# schematic.net
KiCad netlist of a schematic drawn in EAGLE
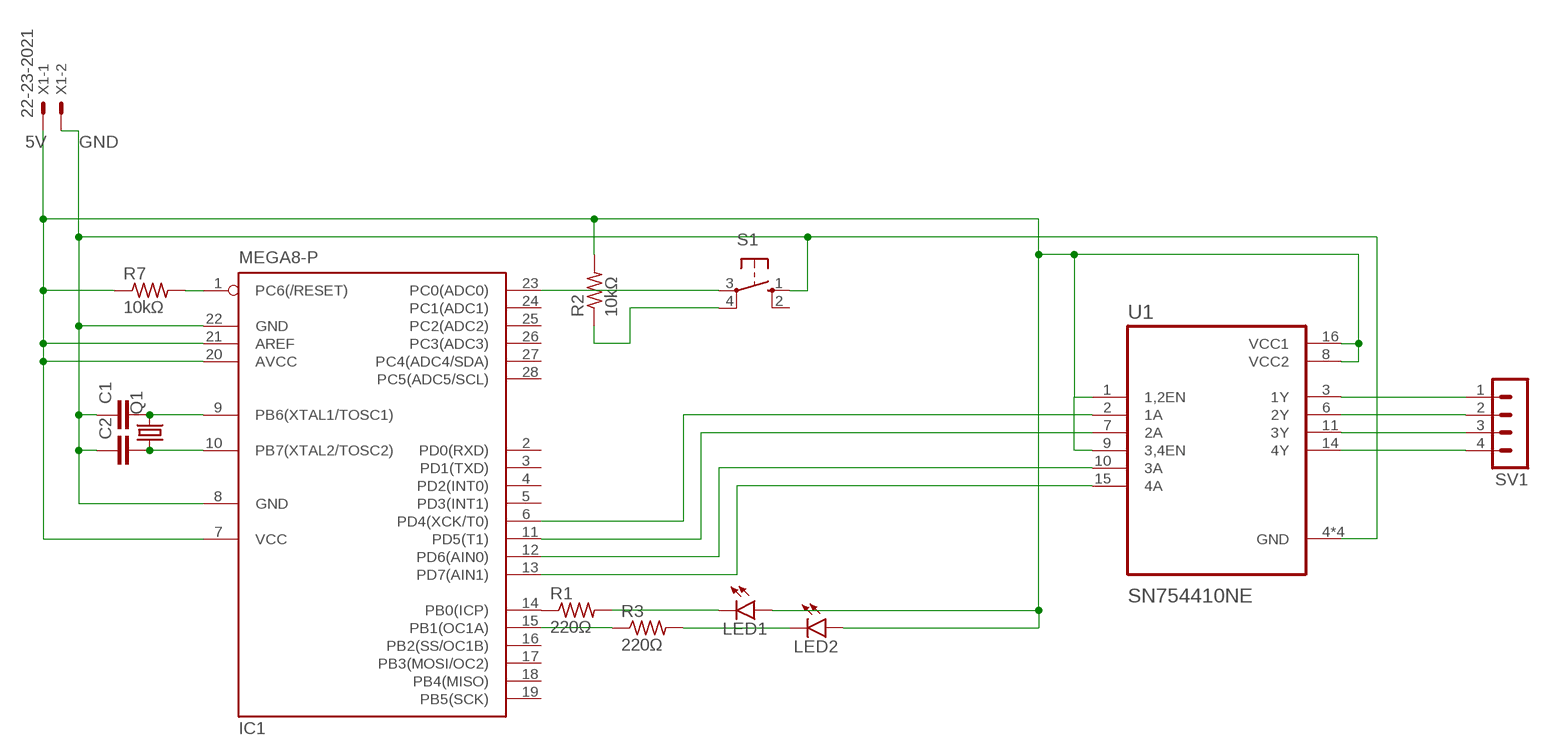
[diagram p0: schematic, sheet 1]

(export (version "E")
  (design (tool "Eeschema 10.0.6"))
  (components
    (comp (ref "C1")
      (value "C2,5-3")
      (footprint "eagle-import:C2.5-3")
      (libsource (lib "eagle-import") (part "C2,5-3"))
    )
    (comp (ref "C2")
      (value "C2,5-3")
      (footprint "eagle-import:C2.5-3")
      (libsource (lib "eagle-import") (part "C2,5-3"))
    )
    (comp (ref "IC1")
      (value "MEGA8-P")
      (footprint "eagle-import:DIL28-3")
      (libsource (lib "eagle-import") (part "MEGA8-P"))
    )
    (comp (ref "LED1")
      (value "LED")
      (footprint "eagle-import:SMARTLED-TTW")
      (libsource (lib "eagle-import") (part "LED"))
    )
    (comp (ref "LED2")
      (value "LED")
      (footprint "eagle-import:SMARTLED-TTW")
      (libsource (lib "eagle-import") (part "LED"))
    )
    (comp (ref "Q1")
      (value "CRYSTALHC18U-V")
      (footprint "eagle-import:HC18U-V")
      (libsource (lib "eagle-import") (part "CRYSTALHC18U-V"))
    )
    (comp (ref "R1")
      (value "220Ω")
      (footprint "eagle-import:0204V")
      (libsource (lib "eagle-import") (part "R-US_0204/2V"))
    )
    (comp (ref "R2")
      (value "10kΩ")
      (footprint "eagle-import:0204V")
      (libsource (lib "eagle-import") (part "R-US_0204/2V"))
    )
    (comp (ref "R3")
      (value "220Ω")
      (footprint "eagle-import:0204V")
      (libsource (lib "eagle-import") (part "R-US_0204/2V"))
    )
    (comp (ref "R7")
      (value "10kΩ")
      (footprint "eagle-import:0204V")
      (libsource (lib "eagle-import") (part "R-US_0204/2V"))
    )
    (comp (ref "S1")
      (value "10-XX")
      (footprint "eagle-import:B3F-10XX")
      (fields (field (name "MPN") "B3F-1000"))
      (libsource (lib "eagle-import") (part "10-XX"))
    )
    (comp (ref "SV1")
      (value "MA04-1")
      (footprint "eagle-import:MA04-1")
      (libsource (lib "eagle-import") (part "MA04-1"))
    )
    (comp (ref "U1")
      (value "SN754410NE")
      (footprint "eagle-import:DIP762W45P254L1980H508Q16")
      (fields (field (name "MF") "Texas Instruments"))
      (libsource (lib "eagle-import") (part "SN754410NE"))
    )
    (comp (ref "X1")
      (value "22-23-2021")
      (footprint "eagle-import:22-23-2021")
      (fields (field (name "MF") "MOLEX"))
      (libsource (lib "eagle-import") (part "22-23-2021"))
    )
  )
  (nets
    (net (code "1") (name "/5V") (class "Default")
      (node (ref "IC1") (pin "20") (pinfunction "AVCC_20") (pintype "power_in"))
      (node (ref "IC1") (pin "21") (pinfunction "AREF_21") (pintype "passive"))
      (node (ref "IC1") (pin "7") (pinfunction "VCC_7") (pintype "power_in"))
      (node (ref "LED1") (pin "A@1") (pinfunction "A_A@1") (pintype "passive"))
      (node (ref "LED2") (pin "A@1") (pinfunction "A_A@1") (pintype "passive"))
      (node (ref "R2") (pin "2") (pinfunction "2_2") (pintype "passive"))
      (node (ref "R7") (pin "1") (pinfunction "1_1") (pintype "passive"))
      (node (ref "U1") (pin "1") (pinfunction "1,2EN_1") (pintype "input"))
      (node (ref "U1") (pin "16") (pinfunction "VCC1_16") (pintype "power_in"))
      (node (ref "U1") (pin "8") (pinfunction "VCC2_8") (pintype "power_in"))
      (node (ref "U1") (pin "9") (pinfunction "3,4EN_9") (pintype "input"))
      (node (ref "X1") (pin "1") (pinfunction "S_1") (pintype "passive"))
    )
    (net (code "2") (name "/GND") (class "Default")
      (node (ref "C1") (pin "1") (pinfunction "1_1") (pintype "passive"))
      (node (ref "C2") (pin "1") (pinfunction "1_1") (pintype "passive"))
      (node (ref "IC1") (pin "22") (pinfunction "GND_22") (pintype "power_in"))
      (node (ref "IC1") (pin "8") (pinfunction "GND_8") (pintype "power_in"))
      (node (ref "S1") (pin "1") (pinfunction "S_1") (pintype "passive"))
      (node (ref "U1") (pin "12") (pinfunction "GND_12") (pintype "power_in"))
      (node (ref "U1") (pin "13") (pinfunction "GND_13") (pintype "power_in"))
      (node (ref "U1") (pin "4") (pinfunction "GND_4") (pintype "power_in"))
      (node (ref "U1") (pin "5") (pinfunction "GND_5") (pintype "power_in"))
      (node (ref "X1") (pin "2") (pinfunction "S_2") (pintype "passive"))
    )
    (net (code "3") (name "Net-(IC1-PB0(ICP))") (class "Default")
      (node (ref "IC1") (pin "14") (pinfunction "PB0(ICP)_14") (pintype "bidirectional"))
      (node (ref "R1") (pin "1") (pinfunction "1_1") (pintype "passive"))
    )
    (net (code "4") (name "Net-(IC1-PB1(OC1A))") (class "Default")
      (node (ref "IC1") (pin "15") (pinfunction "PB1(OC1A)_15") (pintype "bidirectional"))
      (node (ref "R3") (pin "1") (pinfunction "1_1") (pintype "passive"))
    )
    (net (code "5") (name "Net-(IC1-PB6(XTAL1{slash}TOSC1))") (class "Default")
      (node (ref "C1") (pin "2") (pinfunction "2_2") (pintype "passive"))
      (node (ref "IC1") (pin "9") (pinfunction "PB6(XTAL1/TOSC1)_9") (pintype "bidirectional"))
      (node (ref "Q1") (pin "2") (pinfunction "2_2") (pintype "passive"))
    )
    (net (code "6") (name "Net-(IC1-PB7(XTAL2{slash}TOSC2))") (class "Default")
      (node (ref "C2") (pin "2") (pinfunction "2_2") (pintype "passive"))
      (node (ref "IC1") (pin "10") (pinfunction "PB7(XTAL2/TOSC2)_10") (pintype "bidirectional"))
      (node (ref "Q1") (pin "1") (pinfunction "1_1") (pintype "passive"))
    )
    (net (code "7") (name "Net-(IC1-PC0(ADC0))") (class "Default")
      (node (ref "IC1") (pin "23") (pinfunction "PC0(ADC0)_23") (pintype "bidirectional"))
      (node (ref "S1") (pin "3") (pinfunction "P_3") (pintype "passive"))
    )
    (net (code "8") (name "Net-(IC1-PC6({slash}RESET))") (class "Default")
      (node (ref "IC1") (pin "1") (pinfunction "PC6(/RESET)_1") (pintype "bidirectional"))
      (node (ref "R7") (pin "2") (pinfunction "2_2") (pintype "passive"))
    )
    (net (code "9") (name "Net-(IC1-PD4(XCK{slash}T0))") (class "Default")
      (node (ref "IC1") (pin "6") (pinfunction "PD4(XCK/T0)_6") (pintype "bidirectional"))
      (node (ref "U1") (pin "2") (pinfunction "1A_2") (pintype "input"))
    )
    (net (code "10") (name "Net-(IC1-PD5(T1))") (class "Default")
      (node (ref "IC1") (pin "11") (pinfunction "PD5(T1)_11") (pintype "bidirectional"))
      (node (ref "U1") (pin "7") (pinfunction "2A_7") (pintype "input"))
    )
    (net (code "11") (name "Net-(IC1-PD6(AIN0))") (class "Default")
      (node (ref "IC1") (pin "12") (pinfunction "PD6(AIN0)_12") (pintype "bidirectional"))
      (node (ref "U1") (pin "10") (pinfunction "3A_10") (pintype "input"))
    )
    (net (code "12") (name "Net-(IC1-PD7(AIN1))") (class "Default")
      (node (ref "IC1") (pin "13") (pinfunction "PD7(AIN1)_13") (pintype "bidirectional"))
      (node (ref "U1") (pin "15") (pinfunction "4A_15") (pintype "input"))
    )
    (net (code "13") (name "Net-(LED1-C)") (class "Default")
      (node (ref "LED1") (pin "C@1") (pinfunction "C_C@1") (pintype "passive"))
      (node (ref "R1") (pin "2") (pinfunction "2_2") (pintype "passive"))
    )
    (net (code "14") (name "Net-(LED2-C)") (class "Default")
      (node (ref "LED2") (pin "C@1") (pinfunction "C_C@1") (pintype "passive"))
      (node (ref "R3") (pin "2") (pinfunction "2_2") (pintype "passive"))
    )
    (net (code "15") (name "Net-(S1-P1)") (class "Default")
      (node (ref "R2") (pin "1") (pinfunction "1_1") (pintype "passive"))
      (node (ref "S1") (pin "4") (pinfunction "P1_4") (pintype "passive"))
    )
    (net (code "16") (name "Net-(U1-1Y)") (class "Default")
      (node (ref "SV1") (pin "1") (pinfunction "1_1") (pintype "passive"))
      (node (ref "U1") (pin "3") (pinfunction "1Y_3") (pintype "output"))
    )
    (net (code "17") (name "Net-(U1-2Y)") (class "Default")
      (node (ref "SV1") (pin "2") (pinfunction "2_2") (pintype "passive"))
      (node (ref "U1") (pin "6") (pinfunction "2Y_6") (pintype "output"))
    )
    (net (code "18") (name "Net-(U1-3Y)") (class "Default")
      (node (ref "SV1") (pin "3") (pinfunction "3_3") (pintype "passive"))
      (node (ref "U1") (pin "11") (pinfunction "3Y_11") (pintype "output"))
    )
    (net (code "19") (name "Net-(U1-4Y)") (class "Default")
      (node (ref "SV1") (pin "4") (pinfunction "4_4") (pintype "passive"))
      (node (ref "U1") (pin "14") (pinfunction "4Y_14") (pintype "output"))
    )
    (net (code "20") (name "unconnected-(IC1-PB2(SS{slash}OC1B)-Pad16)") (class "Default")
      (node (ref "IC1") (pin "16") (pinfunction "PB2(SS/OC1B)_16") (pintype "bidirectional"))
    )
    (net (code "21") (name "unconnected-(IC1-PB3(MOSI{slash}OC2)-Pad17)") (class "Default")
      (node (ref "IC1") (pin "17") (pinfunction "PB3(MOSI/OC2)_17") (pintype "bidirectional"))
    )
    (net (code "22") (name "unconnected-(IC1-PB4(MISO)-Pad18)") (class "Default")
      (node (ref "IC1") (pin "18") (pinfunction "PB4(MISO)_18") (pintype "bidirectional"))
    )
    (net (code "23") (name "unconnected-(IC1-PB5(SCK)-Pad19)") (class "Default")
      (node (ref "IC1") (pin "19") (pinfunction "PB5(SCK)_19") (pintype "bidirectional"))
    )
    (net (code "24") (name "unconnected-(IC1-PC1(ADC1)-Pad24)") (class "Default")
      (node (ref "IC1") (pin "24") (pinfunction "PC1(ADC1)_24") (pintype "bidirectional"))
    )
    (net (code "25") (name "unconnected-(IC1-PC2(ADC2)-Pad25)") (class "Default")
      (node (ref "IC1") (pin "25") (pinfunction "PC2(ADC2)_25") (pintype "bidirectional"))
    )
    (net (code "26") (name "unconnected-(IC1-PC3(ADC3)-Pad26)") (class "Default")
      (node (ref "IC1") (pin "26") (pinfunction "PC3(ADC3)_26") (pintype "bidirectional"))
    )
    (net (code "27") (name "unconnected-(IC1-PC4(ADC4{slash}SDA)-Pad27)") (class "Default")
      (node (ref "IC1") (pin "27") (pinfunction "PC4(ADC4/SDA)_27") (pintype "bidirectional"))
    )
    (net (code "28") (name "unconnected-(IC1-PC5(ADC5{slash}SCL)-Pad28)") (class "Default")
      (node (ref "IC1") (pin "28") (pinfunction "PC5(ADC5/SCL)_28") (pintype "bidirectional"))
    )
    (net (code "29") (name "unconnected-(IC1-PD0(RXD)-Pad2)") (class "Default")
      (node (ref "IC1") (pin "2") (pinfunction "PD0(RXD)_2") (pintype "bidirectional"))
    )
    (net (code "30") (name "unconnected-(IC1-PD1(TXD)-Pad3)") (class "Default")
      (node (ref "IC1") (pin "3") (pinfunction "PD1(TXD)_3") (pintype "bidirectional"))
    )
    (net (code "31") (name "unconnected-(IC1-PD2(INT0)-Pad4)") (class "Default")
      (node (ref "IC1") (pin "4") (pinfunction "PD2(INT0)_4") (pintype "bidirectional"))
    )
    (net (code "32") (name "unconnected-(IC1-PD3(INT1)-Pad5)") (class "Default")
      (node (ref "IC1") (pin "5") (pinfunction "PD3(INT1)_5") (pintype "bidirectional"))
    )
    (net (code "33") (name "unconnected-(S1-S1-Pad2)") (class "Default")
      (node (ref "S1") (pin "2") (pinfunction "S1_2") (pintype "passive"))
    )
  )
)
